# Power-conn.net
KiCad netlist of a schematic drawn in Altium Designer
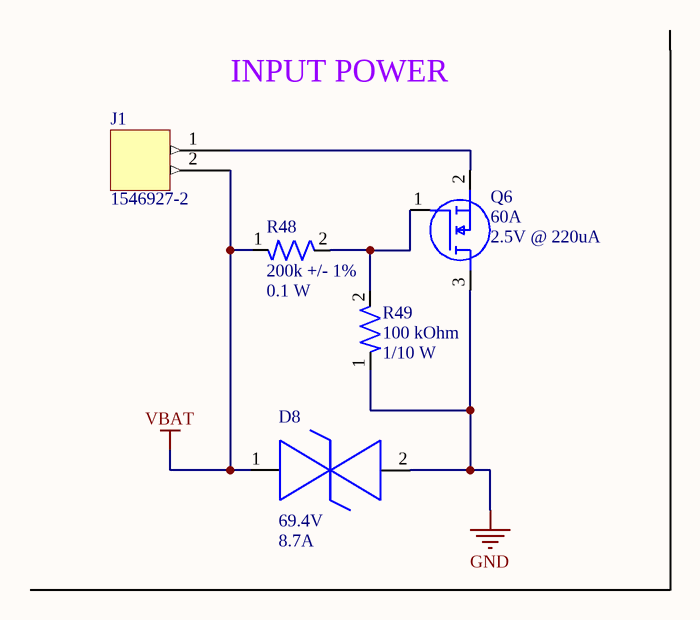
[diagram p0: Power-conn.SchDoc]

(export (version "E")
  (design (tool "Eeschema 10.0.6"))
  (components
    (comp (ref "D8")
      (value "SMBJE43CAH")
      (footprint "DO-214AA (SMBJ)")
      (description "69.4V Clamp 8.7A Ipp Tvs Diode Surface Mount DO-214AA (SMBJ)")
      (fields (field (name "VCLAMP") "69.4V") (field (name "PEAK PULSER CURRENT") "8.7A"))
      (libsource (lib "MasterLib") (part "DIO-69.4V-0001"))
    )
    (comp (ref "J1")
      (value "1546927-2")
      (footprint "CONN-1546927-2")
      (libsource (lib "MasterLib") (part "CON-2POS-0003"))
    )
    (comp (ref "Q6")
      (value "TPH7R006PL,L1Q")
      (footprint "NMOS-8PowerVDFN")
      (description "N-Channel 60 V 60A (Tc) 81W (Tc) Surface Mount 8-SOP Advance (5x5)")
      (fields (field (name "DRAIN CURRENT") "60A") (field (name "VGS") "2.5V @ 220uA"))
      (libsource (lib "MasterLib") (part "NMOS-60A-0001"))
    )
    (comp (ref "R48")
      (value "ERJ-3EKF2003V")
      (footprint "RES-0603")
      (description "200 kOhms ±1% 0.1W, 1/10W Chip Resistor 0603 (1608 Metric) Automotive AEC-Q200 Thick Film")
      (fields
        (field (name "MANUFACTURER") "Panasonic Electronic Components")
        (field (name "RESISTANCE") "200k +/- 1%")
        (field (name "POWER RATING") "0.1 W")
      )
      (libsource (lib "MasterLib") (part "RES-200K-0001"))
    )
    (comp (ref "R49")
      (value "RC0603FR-07100KL")
      (footprint "RES-0603")
      (description "100 kOhms ±1% 0.1W, 1/10W Chip Resistor 0603 (1608 Metric) Moisture Resistant Thick Film")
      (fields
        (field (name "TOLERANCE") "+/- 1%")
        (field (name "RESISTANCE") "100 kOhm")
        (field (name "POWER") "1/10 W")
      )
      (libsource (lib "MasterLib") (part "RES-100K-0003"))
    )
  )
  (nets
    (net (code "1") (name "GND") (class "Default")
      (node (ref "D8") (pin "2") (pintype "passive"))
      (node (ref "Q6") (pin "3") (pinfunction "D_3") (pintype "passive"))
      (node (ref "R49") (pin "1") (pinfunction "1_1") (pintype "passive"))
    )
    (net (code "2") (name "Net-(Q6-G)") (class "Default")
      (node (ref "Q6") (pin "1") (pinfunction "G_1") (pintype "passive"))
      (node (ref "R48") (pin "2") (pinfunction "2_2") (pintype "passive"))
      (node (ref "R49") (pin "2") (pinfunction "2_2") (pintype "passive"))
    )
    (net (code "3") (name "Net-(Q6-S)") (class "Default")
      (node (ref "J1") (pin "1") (pintype "output"))
      (node (ref "Q6") (pin "2") (pinfunction "S_2") (pintype "passive"))
    )
    (net (code "4") (name "VBAT") (class "Default")
      (node (ref "D8") (pin "1") (pintype "passive"))
      (node (ref "J1") (pin "2") (pintype "output"))
      (node (ref "R48") (pin "1") (pinfunction "1_1") (pintype "passive"))
    )
  )
)
